# WPT__RecieverSchDoc.net
KiCad netlist of a schematic drawn in Altium Designer
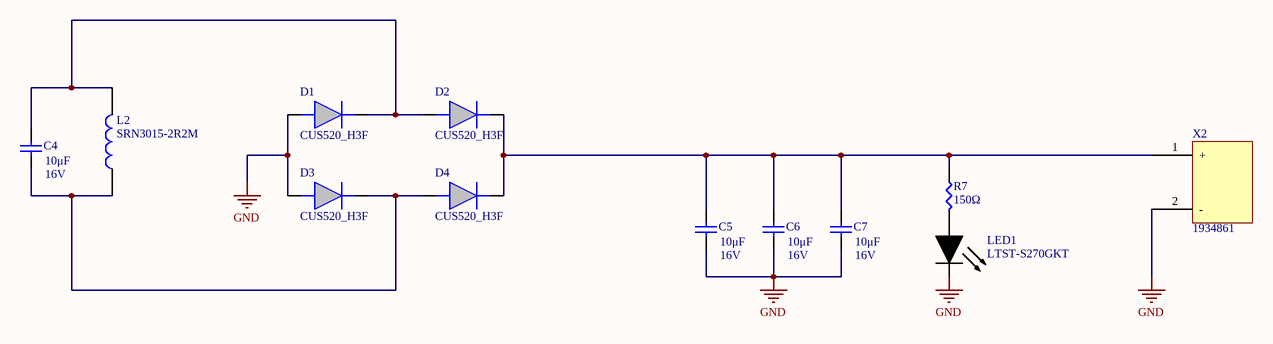
[diagram p0: WPT_.RecieverSchDoc.SchDoc]

(export (version "E")
  (design (tool "Eeschema 10.0.6"))
  (components
    (comp (ref "C4")
      (value "10μF")
      (footprint "CAP0805")
      (description "CAP CER 10UF 16V X5R 0805")
      (fields (field (name "VOLTAGE RATING") "16V") (field (name "Comment") "CL21A106KOCLRNC"))
      (libsource (lib "Bootcamp_Schematic_Library") (part "CL21A106KOCLRNC"))
    )
    (comp (ref "C5")
      (value "10μF")
      (footprint "CAP0805")
      (description "CAP CER 10UF 16V X5R 0805")
      (fields (field (name "VOLTAGE RATING") "16V") (field (name "Comment") "CL21A106KOCLRNC"))
      (libsource (lib "Bootcamp_Schematic_Library") (part "CL21A106KOCLRNC"))
    )
    (comp (ref "C6")
      (value "10μF")
      (footprint "CAP0805")
      (description "CAP CER 10UF 16V X5R 0805")
      (fields (field (name "VOLTAGE RATING") "16V") (field (name "Comment") "CL21A106KOCLRNC"))
      (libsource (lib "Bootcamp_Schematic_Library") (part "CL21A106KOCLRNC"))
    )
    (comp (ref "C7")
      (value "10μF")
      (footprint "CAP0805")
      (description "CAP CER 10UF 16V X5R 0805")
      (fields (field (name "VOLTAGE RATING") "16V") (field (name "Comment") "CL21A106KOCLRNC"))
      (libsource (lib "Bootcamp_Schematic_Library") (part "CL21A106KOCLRNC"))
    )
    (comp (ref "D1")
      (value "CUS520_H3F")
      (footprint "SOD2513X115N")
      (description "Schottky Diodes & Rectifiers Single Low Leakge")
      (fields
        (field (name "MOUSER PART NUMBER") "757-CUS520H3F")
        (field (name "MANUFACTURER_PART_NUMBER") "CUS520,H3F")
      )
      (libsource (lib "Bootcamp_Schematic_Library") (part "CUS520_H3F"))
    )
    (comp (ref "D2")
      (value "CUS520_H3F")
      (footprint "SOD2513X115N")
      (description "Schottky Diodes & Rectifiers Single Low Leakge")
      (fields
        (field (name "MOUSER PART NUMBER") "757-CUS520H3F")
        (field (name "MANUFACTURER_PART_NUMBER") "CUS520,H3F")
      )
      (libsource (lib "Bootcamp_Schematic_Library") (part "CUS520_H3F"))
    )
    (comp (ref "D3")
      (value "CUS520_H3F")
      (footprint "SOD2513X115N")
      (description "Schottky Diodes & Rectifiers Single Low Leakge")
      (fields
        (field (name "MOUSER PART NUMBER") "757-CUS520H3F")
        (field (name "MANUFACTURER_PART_NUMBER") "CUS520,H3F")
      )
      (libsource (lib "Bootcamp_Schematic_Library") (part "CUS520_H3F"))
    )
    (comp (ref "D4")
      (value "CUS520_H3F")
      (footprint "SOD2513X115N")
      (description "Schottky Diodes & Rectifiers Single Low Leakge")
      (fields
        (field (name "MOUSER PART NUMBER") "757-CUS520H3F")
        (field (name "MANUFACTURER_PART_NUMBER") "CUS520,H3F")
      )
      (libsource (lib "Bootcamp_Schematic_Library") (part "CUS520_H3F"))
    )
    (comp (ref "L2")
      (value "SRN3015-2R2M")
      (footprint "INDPM3027X150N")
      (fields (field (name "MOUSER PART NUMBER") "652-SRN3015-2R2M"))
      (libsource (lib "Bootcamp_Schematic_Library") (part "SRN3015-2R2M"))
    )
    (comp (ref "LED1")
      (value "LTST-S270GKT")
      (footprint "LTST-S270GKT")
      (description "LED GREEN CLEAR SMD R/A")
      (libsource (lib "Bootcamp_Schematic_Library") (part "LTST-S270GKT"))
    )
    (comp (ref "R7")
      (value "150Ω")
      (footprint "RES0603")
      (description "RES 150 OHM 1% 1/10W 0603")
      (fields (field (name "Comment") "RC0603FR-07150RL"))
      (libsource (lib "Bootcamp_Schematic_Library") (part "RC0603FR-07150RL"))
    )
    (comp (ref "X2")
      (value "1934861")
      (footprint "1934861")
      (libsource (lib "Bootcamp_Schematic_Library") (part "1934861"))
    )
  )
  (nets
    (net (code "1") (name "GND") (class "Default")
      (node (ref "C5") (pin "1") (pinfunction "1_1") (pintype "passive"))
      (node (ref "C6") (pin "1") (pinfunction "1_1") (pintype "passive"))
      (node (ref "C7") (pin "1") (pinfunction "1_1") (pintype "passive"))
      (node (ref "D1") (pin "2") (pinfunction "A_2") (pintype "passive"))
      (node (ref "D3") (pin "2") (pinfunction "A_2") (pintype "passive"))
      (node (ref "LED1") (pin "1") (pinfunction "1_1") (pintype "passive"))
      (node (ref "X2") (pin "2") (pinfunction "-_2") (pintype "passive"))
    )
    (net (code "2") (name "Net-(D1-K)") (class "Default")
      (node (ref "C4") (pin "2") (pinfunction "2_2") (pintype "passive"))
      (node (ref "D1") (pin "1") (pinfunction "K_1") (pintype "passive"))
      (node (ref "D2") (pin "2") (pinfunction "A_2") (pintype "passive"))
      (node (ref "L2") (pin "2") (pinfunction "2_2") (pintype "passive"))
    )
    (net (code "3") (name "Net-(D2-K)") (class "Default")
      (node (ref "C5") (pin "2") (pinfunction "2_2") (pintype "passive"))
      (node (ref "C6") (pin "2") (pinfunction "2_2") (pintype "passive"))
      (node (ref "C7") (pin "2") (pinfunction "2_2") (pintype "passive"))
      (node (ref "D2") (pin "1") (pinfunction "K_1") (pintype "passive"))
      (node (ref "D4") (pin "1") (pinfunction "K_1") (pintype "passive"))
      (node (ref "R7") (pin "2") (pinfunction "2_2") (pintype "passive"))
      (node (ref "X2") (pin "1") (pinfunction "+_1") (pintype "passive"))
    )
    (net (code "4") (name "Net-(D3-K)") (class "Default")
      (node (ref "C4") (pin "1") (pinfunction "1_1") (pintype "passive"))
      (node (ref "D3") (pin "1") (pinfunction "K_1") (pintype "passive"))
      (node (ref "D4") (pin "2") (pinfunction "A_2") (pintype "passive"))
      (node (ref "L2") (pin "1") (pinfunction "1_1") (pintype "passive"))
    )
    (net (code "5") (name "Net-(LED1-Pad2)") (class "Default")
      (node (ref "LED1") (pin "2") (pinfunction "2_2") (pintype "passive"))
      (node (ref "R7") (pin "1") (pinfunction "1_1") (pintype "passive"))
    )
  )
)
